# Sheet1.net
KiCad netlist of a schematic drawn in Altium Designer
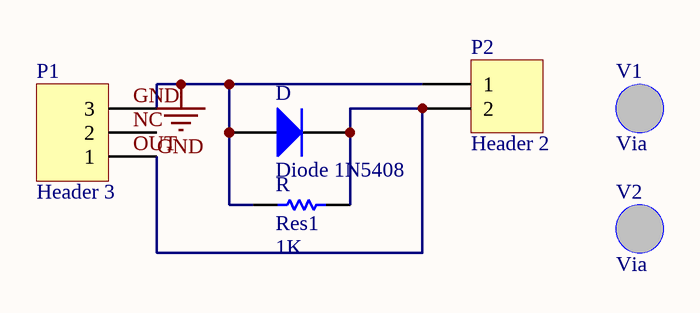
[diagram p0: Sheet1.SchDoc]

(export (version "E")
  (design (tool "Eeschema 10.0.6"))
  (components
    (comp (ref "D")
      (value "Diode 1N5408")
      (footprint "Miscellaneous Devices:6-0805_L")
      (description "3 Amp Medium Power Silicon Rectifier Diode")
      (fields (field (name "PUBLISHER") "Altium Limited"))
      (libsource (lib "Miscellaneous Devices") (part "Diode 1N5408"))
    )
    (comp (ref "P1")
      (value "Header 3")
      (footprint "传感器:sh-2.0")
      (description "Header, 3-Pin")
      (fields (field (name "PUBLISHER") "Altium Limited"))
      (libsource (lib "Miscellaneous Connectors") (part "Header 3"))
    )
    (comp (ref "P2")
      (value "Header 2")
      (footprint "HDR1X2")
      (description "Header, 2-Pin")
      (fields (field (name "PUBLISHER") "Altium Limited"))
      (libsource (lib "Miscellaneous Connectors") (part "Header 2"))
    )
    (comp (ref "R")
      (value "Res1")
      (footprint "Miscellaneous Devices:1608[0603]")
      (description "Resistor")
      (fields (field (name "ALTIUM_VALUE") "1K") (field (name "PUBLISHER") "Altium Limited"))
      (libsource (lib "Miscellaneous Devices") (part "Res1"))
    )
    (comp (ref "V1") (value "Via") (footprint "zhaoyujiu:Via") (libsource (lib "zhaoyujiu") (part "Via")))
    (comp (ref "V2") (value "Via") (footprint "zhaoyujiu:Via") (libsource (lib "zhaoyujiu") (part "Via")))
  )
  (nets
    (net (code "3") (name "GND") (class "Default")
      (node (ref "D") (pin "1") (pinfunction "A_1") (pintype "passive"))
      (node (ref "P1") (pin "3") (pinfunction "3_3") (pintype "passive"))
      (node (ref "P2") (pin "1") (pinfunction "1_1") (pintype "passive"))
      (node (ref "R") (pin "1") (pinfunction "1_1") (pintype "passive"))
    )
    (net (code "4") (name "Net-(D-K)") (class "Default")
      (node (ref "D") (pin "2") (pinfunction "K_2") (pintype "passive"))
      (node (ref "P1") (pin "1") (pinfunction "1_1") (pintype "passive"))
      (node (ref "P2") (pin "2") (pinfunction "2_2") (pintype "passive"))
      (node (ref "R") (pin "2") (pinfunction "2_2") (pintype "passive"))
    )
    (net (code "5") (name "unconnected-(P1-Pad2)") (class "Default")
      (node (ref "P1") (pin "2") (pinfunction "2_2") (pintype "passive"))
    )
  )
)
